# CPU.net
KiCad netlist of a schematic drawn in Altium Designer
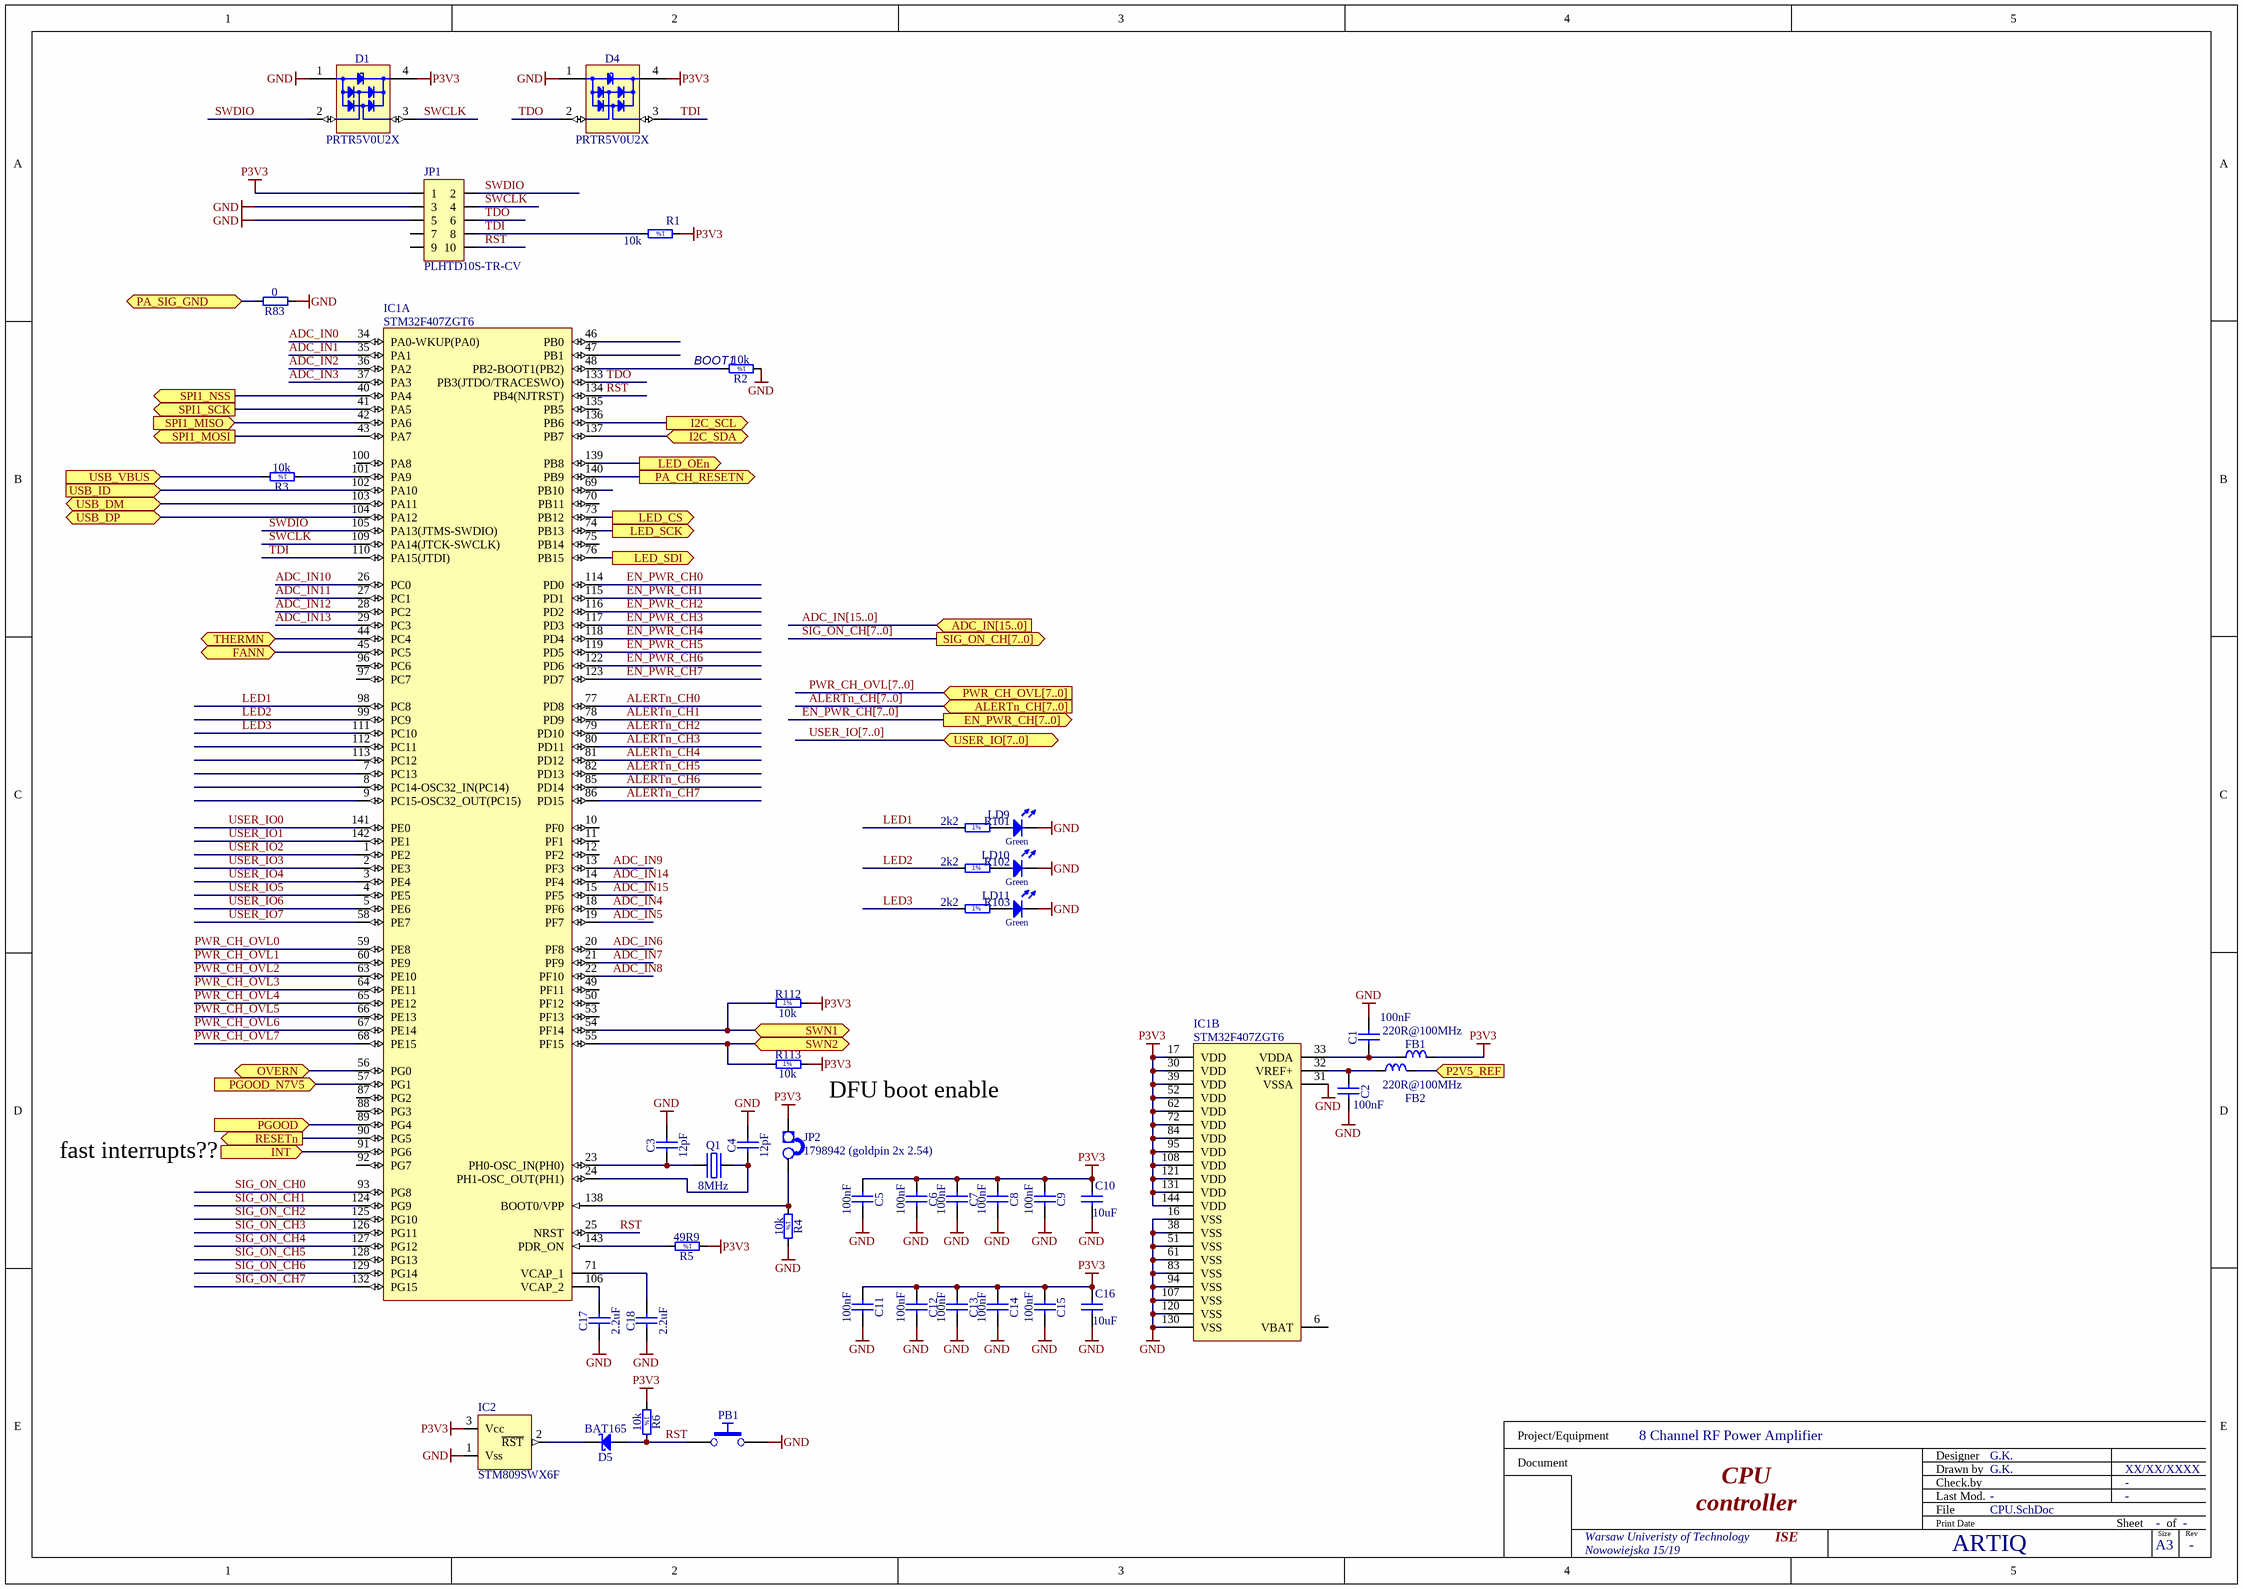
[diagram p0: CPU.SchDoc]

(export (version "E")
  (design (tool "Eeschema 10.0.6"))
  (components
    (comp (ref "C1")
      (value "100nF")
      (footprint "CAPC1005X55N")
      (description "Non-polarised capacitor")
      (fields
        (field (name "PART NUMBER") "CC0402_100NF_16V_10%_X7R")
        (field (name "VOLTAGE") "16V")
        (field (name "AUTHOR") "CERN DEM JLC")
      )
      (libsource (lib "Capacitors") (part "Capacitor - non polarized"))
    )
    (comp (ref "C2")
      (value "100nF")
      (footprint "CAPC1005X55N")
      (description "Non-polarised capacitor")
      (fields
        (field (name "PART NUMBER") "CC0402_100NF_16V_10%_X7R")
        (field (name "VOLTAGE") "16V")
        (field (name "AUTHOR") "CERN DEM JLC")
      )
      (libsource (lib "Capacitors") (part "Capacitor - non polarized"))
    )
    (comp (ref "C3")
      (value "12pF")
      (footprint "CAPC1005X55N")
      (description "Non-polarised capacitor")
      (fields
        (field (name "PART NUMBER") "CC0402_12PF_50V_5%_C0G")
        (field (name "VOLTAGE") "50V")
        (field (name "AUTHOR") "CERN DEM JLC")
      )
      (libsource (lib "Capacitors") (part "Capacitor - non polarized"))
    )
    (comp (ref "C4")
      (value "12pF")
      (footprint "CAPC1005X55N")
      (description "Non-polarised capacitor")
      (fields
        (field (name "PART NUMBER") "CC0402_12PF_50V_5%_C0G")
        (field (name "VOLTAGE") "50V")
        (field (name "AUTHOR") "CERN DEM JLC")
      )
      (libsource (lib "Capacitors") (part "Capacitor - non polarized"))
    )
    (comp (ref "C5")
      (value "100nF")
      (footprint "CAPC1005X55N")
      (description "Non-polarised capacitor")
      (fields
        (field (name "PART NUMBER") "CC0402_100NF_16V_10%_X7R")
        (field (name "VOLTAGE") "16V")
        (field (name "AUTHOR") "CERN DEM JLC")
      )
      (libsource (lib "Capacitors") (part "Capacitor - non polarized"))
    )
    (comp (ref "C6")
      (value "100nF")
      (footprint "CAPC1005X55N")
      (description "Non-polarised capacitor")
      (fields
        (field (name "PART NUMBER") "CC0402_100NF_16V_10%_X7R")
        (field (name "VOLTAGE") "16V")
        (field (name "AUTHOR") "CERN DEM JLC")
      )
      (libsource (lib "Capacitors") (part "Capacitor - non polarized"))
    )
    (comp (ref "C7")
      (value "100nF")
      (footprint "CAPC1005X55N")
      (description "Non-polarised capacitor")
      (fields
        (field (name "PART NUMBER") "CC0402_100NF_16V_10%_X7R")
        (field (name "VOLTAGE") "16V")
        (field (name "AUTHOR") "CERN DEM JLC")
      )
      (libsource (lib "Capacitors") (part "Capacitor - non polarized"))
    )
    (comp (ref "C8")
      (value "100nF")
      (footprint "CAPC1005X55N")
      (description "Non-polarised capacitor")
      (fields
        (field (name "PART NUMBER") "CC0402_100NF_16V_10%_X7R")
        (field (name "VOLTAGE") "16V")
        (field (name "AUTHOR") "CERN DEM JLC")
      )
      (libsource (lib "Capacitors") (part "Capacitor - non polarized"))
    )
    (comp (ref "C9")
      (value "100nF")
      (footprint "CAPC1005X55N")
      (description "Non-polarised capacitor")
      (fields
        (field (name "PART NUMBER") "CC0402_100NF_16V_10%_X7R")
        (field (name "VOLTAGE") "16V")
        (field (name "AUTHOR") "CERN DEM JLC")
      )
      (libsource (lib "Capacitors") (part "Capacitor - non polarized"))
    )
    (comp (ref "C10")
      (value "10uF")
      (footprint "CAPC2012X135N")
      (description "Non-polarised capacitor")
      (fields
        (field (name "PART NUMBER") "CC0805_10UF_10V_10%_X7R")
        (field (name "VOLTAGE") "10V")
        (field (name "AUTHOR") "CERN DEM JLC")
      )
      (libsource (lib "Capacitors") (part "Capacitor - non polarized"))
    )
    (comp (ref "C11")
      (value "100nF")
      (footprint "CAPC1005X55N")
      (description "Non-polarised capacitor")
      (fields
        (field (name "PART NUMBER") "CC0402_100NF_16V_10%_X7R")
        (field (name "VOLTAGE") "16V")
        (field (name "AUTHOR") "CERN DEM JLC")
      )
      (libsource (lib "Capacitors") (part "Capacitor - non polarized"))
    )
    (comp (ref "C12")
      (value "100nF")
      (footprint "CAPC1005X55N")
      (description "Non-polarised capacitor")
      (fields
        (field (name "PART NUMBER") "CC0402_100NF_16V_10%_X7R")
        (field (name "VOLTAGE") "16V")
        (field (name "AUTHOR") "CERN DEM JLC")
      )
      (libsource (lib "Capacitors") (part "Capacitor - non polarized"))
    )
    (comp (ref "C13")
      (value "100nF")
      (footprint "CAPC1005X55N")
      (description "Non-polarised capacitor")
      (fields
        (field (name "PART NUMBER") "CC0402_100NF_16V_10%_X7R")
        (field (name "VOLTAGE") "16V")
        (field (name "AUTHOR") "CERN DEM JLC")
      )
      (libsource (lib "Capacitors") (part "Capacitor - non polarized"))
    )
    (comp (ref "C14")
      (value "100nF")
      (footprint "CAPC1005X55N")
      (description "Non-polarised capacitor")
      (fields
        (field (name "PART NUMBER") "CC0402_100NF_16V_10%_X7R")
        (field (name "VOLTAGE") "16V")
        (field (name "AUTHOR") "CERN DEM JLC")
      )
      (libsource (lib "Capacitors") (part "Capacitor - non polarized"))
    )
    (comp (ref "C15")
      (value "100nF")
      (footprint "CAPC1005X55N")
      (description "Non-polarised capacitor")
      (fields
        (field (name "PART NUMBER") "CC0402_100NF_16V_10%_X7R")
        (field (name "VOLTAGE") "16V")
        (field (name "AUTHOR") "CERN DEM JLC")
      )
      (libsource (lib "Capacitors") (part "Capacitor - non polarized"))
    )
    (comp (ref "C16")
      (value "10uF")
      (footprint "CAPC2012X135N")
      (description "Non-polarised capacitor")
      (fields
        (field (name "PART NUMBER") "CC0805_10UF_10V_10%_X7R")
        (field (name "VOLTAGE") "10V")
        (field (name "AUTHOR") "CERN DEM JLC")
      )
      (libsource (lib "Capacitors") (part "Capacitor - non polarized"))
    )
    (comp (ref "C17")
      (value "2.2uF")
      (footprint "CAPC1608X90N")
      (description "Non-polarised capacitor")
      (fields
        (field (name "PART NUMBER") "CC0603_2.2UF_10V_20%_X7R")
        (field (name "VOLTAGE") "10V")
        (field (name "AUTHOR") "CERN DEM JLC")
      )
      (libsource (lib "Capacitors") (part "Capacitor - non polarized"))
    )
    (comp (ref "C18")
      (value "2.2uF")
      (footprint "CAPC1608X90N")
      (description "Non-polarised capacitor")
      (fields
        (field (name "PART NUMBER") "CC0603_2.2UF_10V_20%_X7R")
        (field (name "VOLTAGE") "10V")
        (field (name "AUTHOR") "CERN DEM JLC")
      )
      (libsource (lib "Capacitors") (part "Capacitor - non polarized"))
    )
    (comp (ref "D1")
      (value "PRTR5V0U2X")
      (footprint "SOT190P230X110-4N")
      (description "Ultra Low Capacitance Double Rail-to-Rail ESD Protection Diode")
      (fields
        (field (name "VOLTAGE") "5.5V")
        (field (name "MANUFACTURER") "NXP SEMICONDUCTORS")
        (field (name "AUTHOR") "CERN DEM JLC")
      )
      (libsource (lib "ICs And Semiconductors") (part "PRTR5V0U2X"))
    )
    (comp (ref "D4")
      (value "PRTR5V0U2X")
      (footprint "SOT190P230X110-4N")
      (description "Ultra Low Capacitance Double Rail-to-Rail ESD Protection Diode")
      (fields
        (field (name "VOLTAGE") "5.5V")
        (field (name "MANUFACTURER") "NXP SEMICONDUCTORS")
        (field (name "AUTHOR") "CERN DEM JLC")
      )
      (libsource (lib "ICs And Semiconductors") (part "PRTR5V0U2X"))
    )
    (comp (ref "D5")
      (value "BAT165")
      (footprint "SOD2512X110N")
      (description "Schottky Diode")
      (fields
        (field (name "VOLTAGE") "40V")
        (field (name "POWER") "750mA")
        (field (name "AUTHOR") "CERN DEM JLC")
      )
      (libsource (lib "ICs And Semiconductors") (part "Diode Schottky"))
    )
    (comp (ref "FB1")
      (value "220R@100MHz")
      (footprint "INDC2012X105N")
      (description "Inductor")
      (fields
        (field (name "PART NUMBER") "IND0805_MURATA_BLM21PG221SN1D")
        (field (name "POWER") "2A")
        (field (name "AUTHOR") "CERN DEM JLC")
      )
      (libsource (lib "Inductors & Transformers") (part "Inductor"))
    )
    (comp (ref "FB2")
      (value "220R@100MHz")
      (footprint "INDC2012X105N")
      (description "Inductor")
      (fields
        (field (name "PART NUMBER") "IND0805_MURATA_BLM21PG221SN1D")
        (field (name "POWER") "2A")
        (field (name "AUTHOR") "CERN DEM JLC")
      )
      (libsource (lib "Inductors & Transformers") (part "Inductor"))
    )
    (comp (ref "IC1")
      (value "STM32F407ZGT6")
      (footprint "QFP50P2200X2200X160-144N")
      (fields (field (name "MANUFACTURER") "ST MICROELECTRONICS") (field (name "AUTHOR") "CERN DEM MR"))
      (libsource (lib "ICs And Semiconductors") (part "STM32F407ZGT6"))
    )
    (comp (ref "IC2")
      (value "STM809SWX6F")
      (footprint "SOT-23")
      (description "2.93V  Reset circuit")
      (libsource (lib "LIBRARY_SCH") (part "VMON_STM809"))
    )
    (comp (ref "JP1")
      (value "PLHTD10S-TR-CV")
      (footprint "PLHTD10S-TR-CV")
      (description "1.27 mm dual row goldpin (Maritex)")
      (libsource (lib "LIBRARY_SCH") (part "CON_2x5 1.27 SMT Male"))
    )
    (comp (ref "JP2")
      (value "1798942 (goldpin 2x 2.54)")
      (footprint "jump")
      (description "Jumper")
      (libsource (lib "LIBRARY_SCH") (part "JUMPER"))
    )
    (comp (ref "LD9")
      (value "Green")
      (footprint "LED_OSRAM_LGL29K")
      (description "LED Green 1C 2A")
      (fields
        (field (name "PART NUMBER") "LED_OSRAM_LG L29K-G2J1-24-Z")
        (field (name "MANUFACTURER") "OSRAM")
        (field (name "AUTHOR") "CERN DEM JLC")
      )
      (libsource (lib "ICs And Semiconductors") (part "LED Green 1C 2A"))
    )
    (comp (ref "LD10")
      (value "Green")
      (footprint "LED_OSRAM_LGL29K")
      (description "LED Green 1C 2A")
      (fields
        (field (name "PART NUMBER") "LED_OSRAM_LG L29K-G2J1-24-Z")
        (field (name "MANUFACTURER") "OSRAM")
        (field (name "AUTHOR") "CERN DEM JLC")
      )
      (libsource (lib "ICs And Semiconductors") (part "LED Green 1C 2A"))
    )
    (comp (ref "LD11")
      (value "Green")
      (footprint "LED_OSRAM_LGL29K")
      (description "LED Green 1C 2A")
      (fields
        (field (name "PART NUMBER") "LED_OSRAM_LG L29K-G2J1-24-Z")
        (field (name "MANUFACTURER") "OSRAM")
        (field (name "AUTHOR") "CERN DEM JLC")
      )
      (libsource (lib "ICs And Semiconductors") (part "LED Green 1C 2A"))
    )
    (comp (ref "PB1")
      (value "Push Button")
      (footprint "PB_TYCO_FSMSM")
      (description "Push-Button Switch SPDT")
      (fields
        (field (name "PART NUMBER") "PB_TYCO_FSMSM")
        (field (name "MANUFACTURER") "TYCO ELECTRONICS")
        (field (name "AUTHOR") "CERN DEM JLC")
      )
      (libsource (lib "Eletro-mechanical") (part "PB SPST 1NO-2NO"))
    )
    (comp (ref "Q1")
      (value "8MHz")
      (footprint "XTAL_TXC_7A")
      (description "Quartz Crystal")
      (fields
        (field (name "PART NUMBER") "XTAL_8MHZ_TXC_7A-8.000MAAE-T")
        (field (name "MANUFACTURER") "TXC CORPORATION")
        (field (name "AUTHOR") "CERN DEM JLC")
      )
      (libsource (lib "ICs And Semiconductors") (part "Quartz Crystal"))
    )
    (comp (ref "R1")
      (value "10k")
      (footprint "RESC1005X40N")
      (description "Resistor - 1%")
      (fields
        (field (name "PART NUMBER") "R0402_10K_1%_0.0625W_100PPM")
        (field (name "POWER") "0.0625W")
        (field (name "AUTHOR") "CERN DEM JLC")
      )
      (libsource (lib "Resistors") (part "Resistor - 1%"))
    )
    (comp (ref "R2")
      (value "10k")
      (footprint "RESC1005X40N")
      (description "Resistor - 1%")
      (fields
        (field (name "PART NUMBER") "R0402_10K_1%_0.0625W_100PPM")
        (field (name "POWER") "0.0625W")
        (field (name "AUTHOR") "CERN DEM JLC")
      )
      (libsource (lib "Resistors") (part "Resistor - 1%"))
    )
    (comp (ref "R3")
      (value "10k")
      (footprint "RESC1005X40N")
      (description "Resistor - 1%")
      (fields
        (field (name "PART NUMBER") "R0402_10K_1%_0.0625W_100PPM")
        (field (name "POWER") "0.0625W")
        (field (name "AUTHOR") "CERN DEM JLC")
      )
      (libsource (lib "Resistors") (part "Resistor - 1%"))
    )
    (comp (ref "R4")
      (value "10k")
      (footprint "RESC1005X40N")
      (description "Resistor - 1%")
      (fields
        (field (name "PART NUMBER") "R0402_10K_1%_0.0625W_100PPM")
        (field (name "POWER") "0.0625W")
        (field (name "AUTHOR") "CERN DEM JLC")
      )
      (libsource (lib "Resistors") (part "Resistor - 1%"))
    )
    (comp (ref "R5")
      (value "49R9")
      (footprint "RESC1005X40N")
      (description "Resistor - 1%")
      (fields
        (field (name "PART NUMBER") "R0402_49R9_1%_0.0625W_100PPM")
        (field (name "POWER") "0.0625W")
        (field (name "AUTHOR") "CERN DEM JLC")
      )
      (libsource (lib "Resistors") (part "Resistor - 1%"))
    )
    (comp (ref "R6")
      (value "10k")
      (footprint "RESC1005X40N")
      (description "Resistor - 1%")
      (fields
        (field (name "PART NUMBER") "R0402_10K_1%_0.0625W_100PPM")
        (field (name "POWER") "0.0625W")
        (field (name "AUTHOR") "CERN DEM JLC")
      )
      (libsource (lib "Resistors") (part "Resistor - 1%"))
    )
    (comp (ref "R83")
      (value "0")
      (footprint "RESC1005X40N")
      (description "Resistor")
      (fields
        (field (name "PART NUMBER") "R0402_0R_JUMPER")
        (field (name "MANUFACTURER") "GENERIC")
        (field (name "AUTHOR") "CERN DEM JLC")
      )
      (libsource (lib "Resistors") (part "Resistor"))
    )
    (comp (ref "R101")
      (value "2k2")
      (footprint "RESC1005X40N")
      (description "Resistor - 1%")
      (fields
        (field (name "PART NUMBER") "R0402_2K2_1%_0.0625W_100PPM")
        (field (name "POWER") "0.0625W")
        (field (name "AUTHOR") "CERN DEM JLC")
      )
      (libsource (lib "Resistors") (part "Resistor - 1%"))
    )
    (comp (ref "R102")
      (value "2k2")
      (footprint "RESC1005X40N")
      (description "Resistor - 1%")
      (fields
        (field (name "PART NUMBER") "R0402_2K2_1%_0.0625W_100PPM")
        (field (name "POWER") "0.0625W")
        (field (name "AUTHOR") "CERN DEM JLC")
      )
      (libsource (lib "Resistors") (part "Resistor - 1%"))
    )
    (comp (ref "R103")
      (value "2k2")
      (footprint "RESC1005X40N")
      (description "Resistor - 1%")
      (fields
        (field (name "PART NUMBER") "R0402_2K2_1%_0.0625W_100PPM")
        (field (name "POWER") "0.0625W")
        (field (name "AUTHOR") "CERN DEM JLC")
      )
      (libsource (lib "Resistors") (part "Resistor - 1%"))
    )
    (comp (ref "R112")
      (value "10k")
      (footprint "RESC1005X40N")
      (description "Resistor - 1%")
      (fields
        (field (name "PART NUMBER") "R0402_10K_1%_0.0625W_100PPM")
        (field (name "POWER") "0.0625W")
        (field (name "AUTHOR") "CERN DEM JLC")
      )
      (libsource (lib "Resistors") (part "Resistor - 1%"))
    )
    (comp (ref "R113")
      (value "10k")
      (footprint "RESC1005X40N")
      (description "Resistor - 1%")
      (fields
        (field (name "PART NUMBER") "R0402_10K_1%_0.0625W_100PPM")
        (field (name "POWER") "0.0625W")
        (field (name "AUTHOR") "CERN DEM JLC")
      )
      (libsource (lib "Resistors") (part "Resistor - 1%"))
    )
  )
  (nets
    (net (code "1") (name "/ADC_IN0") (class "Default")
      (node (ref "IC1") (pin "34") (pinfunction "PA0-WKUP(PA0)_34") (pintype "bidirectional"))
    )
    (net (code "2") (name "/ADC_IN1") (class "Default")
      (node (ref "IC1") (pin "35") (pinfunction "PA1_35") (pintype "bidirectional"))
    )
    (net (code "3") (name "/ADC_IN2") (class "Default")
      (node (ref "IC1") (pin "36") (pinfunction "PA2_36") (pintype "bidirectional"))
    )
    (net (code "4") (name "/ADC_IN3") (class "Default")
      (node (ref "IC1") (pin "37") (pinfunction "PA3_37") (pintype "bidirectional"))
    )
    (net (code "5") (name "/ADC_IN4") (class "Default")
      (node (ref "IC1") (pin "18") (pinfunction "PF6_18") (pintype "bidirectional"))
    )
    (net (code "6") (name "/ADC_IN5") (class "Default")
      (node (ref "IC1") (pin "19") (pinfunction "PF7_19") (pintype "bidirectional"))
    )
    (net (code "7") (name "/ADC_IN6") (class "Default")
      (node (ref "IC1") (pin "20") (pinfunction "PF8_20") (pintype "bidirectional"))
    )
    (net (code "8") (name "/ADC_IN7") (class "Default")
      (node (ref "IC1") (pin "21") (pinfunction "PF9_21") (pintype "bidirectional"))
    )
    (net (code "9") (name "/ADC_IN8") (class "Default")
      (node (ref "IC1") (pin "22") (pinfunction "PF10_22") (pintype "bidirectional"))
    )
    (net (code "10") (name "/ADC_IN9") (class "Default")
      (node (ref "IC1") (pin "13") (pinfunction "PF3_13") (pintype "bidirectional"))
    )
    (net (code "11") (name "/ADC_IN10") (class "Default")
      (node (ref "IC1") (pin "26") (pinfunction "PC0_26") (pintype "bidirectional"))
    )
    (net (code "12") (name "/ADC_IN11") (class "Default")
      (node (ref "IC1") (pin "27") (pinfunction "PC1_27") (pintype "bidirectional"))
    )
    (net (code "13") (name "/ADC_IN12") (class "Default")
      (node (ref "IC1") (pin "28") (pinfunction "PC2_28") (pintype "bidirectional"))
    )
    (net (code "14") (name "/ADC_IN13") (class "Default")
      (node (ref "IC1") (pin "29") (pinfunction "PC3_29") (pintype "bidirectional"))
    )
    (net (code "15") (name "/ADC_IN14") (class "Default")
      (node (ref "IC1") (pin "14") (pinfunction "PF4_14") (pintype "bidirectional"))
    )
    (net (code "16") (name "/ADC_IN15") (class "Default")
      (node (ref "IC1") (pin "15") (pinfunction "PF5_15") (pintype "bidirectional"))
    )
    (net (code "18") (name "/ALERTn_CH0") (class "Default")
      (node (ref "IC1") (pin "77") (pinfunction "PD8_77") (pintype "bidirectional"))
    )
    (net (code "19") (name "/ALERTn_CH1") (class "Default")
      (node (ref "IC1") (pin "78") (pinfunction "PD9_78") (pintype "bidirectional"))
    )
    (net (code "20") (name "/ALERTn_CH2") (class "Default")
      (node (ref "IC1") (pin "79") (pinfunction "PD10_79") (pintype "bidirectional"))
    )
    (net (code "21") (name "/ALERTn_CH3") (class "Default")
      (node (ref "IC1") (pin "80") (pinfunction "PD11_80") (pintype "bidirectional"))
    )
    (net (code "22") (name "/ALERTn_CH4") (class "Default")
      (node (ref "IC1") (pin "81") (pinfunction "PD12_81") (pintype "bidirectional"))
    )
    (net (code "23") (name "/ALERTn_CH5") (class "Default")
      (node (ref "IC1") (pin "82") (pinfunction "PD13_82") (pintype "bidirectional"))
    )
    (net (code "24") (name "/ALERTn_CH6") (class "Default")
      (node (ref "IC1") (pin "85") (pinfunction "PD14_85") (pintype "bidirectional"))
    )
    (net (code "25") (name "/ALERTn_CH7") (class "Default")
      (node (ref "IC1") (pin "86") (pinfunction "PD15_86") (pintype "bidirectional"))
    )
    (net (code "27") (name "/EN_PWR_CH0") (class "Default")
      (node (ref "IC1") (pin "114") (pinfunction "PD0_114") (pintype "bidirectional"))
    )
    (net (code "28") (name "/EN_PWR_CH1") (class "Default")
      (node (ref "IC1") (pin "115") (pinfunction "PD1_115") (pintype "bidirectional"))
    )
    (net (code "29") (name "/EN_PWR_CH2") (class "Default")
      (node (ref "IC1") (pin "116") (pinfunction "PD2_116") (pintype "bidirectional"))
    )
    (net (code "30") (name "/EN_PWR_CH3") (class "Default")
      (node (ref "IC1") (pin "117") (pinfunction "PD3_117") (pintype "bidirectional"))
    )
    (net (code "31") (name "/EN_PWR_CH4") (class "Default")
      (node (ref "IC1") (pin "118") (pinfunction "PD4_118") (pintype "bidirectional"))
    )
    (net (code "32") (name "/EN_PWR_CH5") (class "Default")
      (node (ref "IC1") (pin "119") (pinfunction "PD5_119") (pintype "bidirectional"))
    )
    (net (code "33") (name "/EN_PWR_CH6") (class "Default")
      (node (ref "IC1") (pin "122") (pinfunction "PD6_122") (pintype "bidirectional"))
    )
    (net (code "34") (name "/EN_PWR_CH7") (class "Default")
      (node (ref "IC1") (pin "123") (pinfunction "PD7_123") (pintype "bidirectional"))
    )
    (net (code "36") (name "/FANN") (class "Default")
      (node (ref "IC1") (pin "45") (pinfunction "PC5_45") (pintype "bidirectional"))
    )
    (net (code "37") (name "/I2C_SCL") (class "Default")
      (node (ref "IC1") (pin "136") (pinfunction "PB6_136") (pintype "bidirectional"))
    )
    (net (code "38") (name "/I2C_SDA") (class "Default")
      (node (ref "IC1") (pin "137") (pinfunction "PB7_137") (pintype "bidirectional"))
    )
    (net (code "39") (name "/INT") (class "Default")
      (node (ref "IC1") (pin "91") (pinfunction "PG6_91") (pintype "bidirectional"))
    )
    (net (code "40") (name "/LED1") (class "Default")
      (node (ref "IC1") (pin "98") (pinfunction "PC8_98") (pintype "bidirectional"))
      (node (ref "R101") (pin "1") (pinfunction "1_1") (pintype "passive"))
    )
    (net (code "41") (name "/LED2") (class "Default")
      (node (ref "IC1") (pin "99") (pinfunction "PC9_99") (pintype "bidirectional"))
      (node (ref "R102") (pin "1") (pinfunction "1_1") (pintype "passive"))
    )
    (net (code "42") (name "/LED3") (class "Default")
      (node (ref "IC1") (pin "111") (pinfunction "PC10_111") (pintype "bidirectional"))
      (node (ref "R103") (pin "1") (pinfunction "1_1") (pintype "passive"))
    )
    (net (code "43") (name "/LED_CS") (class "Default")
      (node (ref "IC1") (pin "73") (pinfunction "PB12_73") (pintype "bidirectional"))
    )
    (net (code "44") (name "/LED_OEn") (class "Default")
      (node (ref "IC1") (pin "139") (pinfunction "PB8_139") (pintype "bidirectional"))
    )
    (net (code "45") (name "/LED_SCK") (class "Default")
      (node (ref "IC1") (pin "74") (pinfunction "PB13_74") (pintype "bidirectional"))
    )
    (net (code "46") (name "/LED_SDI") (class "Default")
      (node (ref "IC1") (pin "76") (pinfunction "PB15_76") (pintype "bidirectional"))
    )
    (net (code "47") (name "/OVERN") (class "Default")
      (node (ref "IC1") (pin "56") (pinfunction "PG0_56") (pintype "bidirectional"))
    )
    (net (code "48") (name "/P2V5_REF") (class "Default")
      (node (ref "FB2") (pin "2") (pinfunction "2_2") (pintype "passive"))
    )
    (net (code "49") (name "/PA_CH_RESETN") (class "Default")
      (node (ref "IC1") (pin "140") (pinfunction "PB9_140") (pintype "bidirectional"))
    )
    (net (code "50") (name "/PA_SIG_GND") (class "Default")
      (node (ref "R83") (pin "2") (pinfunction "2_2") (pintype "passive"))
    )
    (net (code "51") (name "/PGOOD") (class "Default")
      (node (ref "IC1") (pin "89") (pinfunction "PG4_89") (pintype "bidirectional"))
    )
    (net (code "52") (name "/PGOOD_N7V5") (class "Default")
      (node (ref "IC1") (pin "57") (pinfunction "PG1_57") (pintype "bidirectional"))
    )
    (net (code "53") (name "/PWR_CH_OVL0") (class "Default")
      (node (ref "IC1") (pin "59") (pinfunction "PE8_59") (pintype "bidirectional"))
    )
    (net (code "54") (name "/PWR_CH_OVL1") (class "Default")
      (node (ref "IC1") (pin "60") (pinfunction "PE9_60") (pintype "bidirectional"))
    )
    (net (code "55") (name "/PWR_CH_OVL2") (class "Default")
      (node (ref "IC1") (pin "63") (pinfunction "PE10_63") (pintype "bidirectional"))
    )
    (net (code "56") (name "/PWR_CH_OVL3") (class "Default")
      (node (ref "IC1") (pin "64") (pinfunction "PE11_64") (pintype "bidirectional"))
    )
    (net (code "57") (name "/PWR_CH_OVL4") (class "Default")
      (node (ref "IC1") (pin "65") (pinfunction "PE12_65") (pintype "bidirectional"))
    )
    (net (code "58") (name "/PWR_CH_OVL5") (class "Default")
      (node (ref "IC1") (pin "66") (pinfunction "PE13_66") (pintype "bidirectional"))
    )
    (net (code "59") (name "/PWR_CH_OVL6") (class "Default")
      (node (ref "IC1") (pin "67") (pinfunction "PE14_67") (pintype "bidirectional"))
    )
    (net (code "60") (name "/PWR_CH_OVL7") (class "Default")
      (node (ref "IC1") (pin "68") (pinfunction "PE15_68") (pintype "bidirectional"))
    )
    (net (code "62") (name "/RESETn") (class "Default")
      (node (ref "IC1") (pin "90") (pinfunction "PG5_90") (pintype "bidirectional"))
    )
    (net (code "63") (name "/RST") (class "Default")
      (node (ref "D5") (pin "2") (pinfunction "A_2") (pintype "passive"))
      (node (ref "IC1") (pin "134") (pinfunction "PB4(NJTRST)_134") (pintype "bidirectional"))
      (node (ref "IC1") (pin "25") (pinfunction "NRST_25") (pintype "bidirectional"))
      (node (ref "JP1") (pin "10") (pinfunction "10_10") (pintype "passive"))
      (node (ref "PB1") (pin "1") (pinfunction "1_1") (pintype "passive"))
      (node (ref "R6") (pin "2") (pinfunction "2_2") (pintype "passive"))
    )
    (net (code "64") (name "/SIG_ON_CH0") (class "Default")
      (node (ref "IC1") (pin "93") (pinfunction "PG8_93") (pintype "bidirectional"))
    )
    (net (code "65") (name "/SIG_ON_CH1") (class "Default")
      (node (ref "IC1") (pin "124") (pinfunction "PG9_124") (pintype "bidirectional"))
    )
    (net (code "66") (name "/SIG_ON_CH2") (class "Default")
      (node (ref "IC1") (pin "125") (pinfunction "PG10_125") (pintype "bidirectional"))
    )
    (net (code "67") (name "/SIG_ON_CH3") (class "Default")
      (node (ref "IC1") (pin "126") (pinfunction "PG11_126") (pintype "bidirectional"))
    )
    (net (code "68") (name "/SIG_ON_CH4") (class "Default")
      (node (ref "IC1") (pin "127") (pinfunction "PG12_127") (pintype "bidirectional"))
    )
    (net (code "69") (name "/SIG_ON_CH5") (class "Default")
      (node (ref "IC1") (pin "128") (pinfunction "PG13_128") (pintype "bidirectional"))
    )
    (net (code "70") (name "/SIG_ON_CH6") (class "Default")
      (node (ref "IC1") (pin "129") (pinfunction "PG14_129") (pintype "bidirectional"))
    )
    (net (code "71") (name "/SIG_ON_CH7") (class "Default")
      (node (ref "IC1") (pin "132") (pinfunction "PG15_132") (pintype "bidirectional"))
    )
    (net (code "73") (name "/SPI1_MISO") (class "Default")
      (node (ref "IC1") (pin "42") (pinfunction "PA6_42") (pintype "bidirectional"))
    )
    (net (code "74") (name "/SPI1_MOSI") (class "Default")
      (node (ref "IC1") (pin "43") (pinfunction "PA7_43") (pintype "bidirectional"))
    )
    (net (code "75") (name "/SPI1_NSS") (class "Default")
      (node (ref "IC1") (pin "40") (pinfunction "PA4_40") (pintype "bidirectional"))
    )
    (net (code "76") (name "/SPI1_SCK") (class "Default")
      (node (ref "IC1") (pin "41") (pinfunction "PA5_41") (pintype "bidirectional"))
    )
    (net (code "77") (name "/SWCLK") (class "Default")
      (node (ref "D1") (pin "3") (pinfunction "I/O2_3") (pintype "bidirectional"))
      (node (ref "IC1") (pin "109") (pinfunction "PA14(JTCK-SWCLK)_109") (pintype "bidirectional"))
      (node (ref "JP1") (pin "4") (pinfunction "4_4") (pintype "passive"))
    )
    (net (code "78") (name "/SWDIO") (class "Default")
      (node (ref "D1") (pin "2") (pinfunction "I/O1_2") (pintype "bidirectional"))
      (node (ref "IC1") (pin "105") (pinfunction "PA13(JTMS-SWDIO)_105") (pintype "bidirectional"))
      (node (ref "JP1") (pin "2") (pinfunction "2_2") (pintype "passive"))
    )
    (net (code "79") (name "/SWN1") (class "Default")
      (node (ref "IC1") (pin "54") (pinfunction "PF14_54") (pintype "bidirectional"))
      (node (ref "R112") (pin "1") (pinfunction "1_1") (pintype "passive"))
    )
    (net (code "80") (name "/SWN2") (class "Default")
      (node (ref "IC1") (pin "55") (pinfunction "PF15_55") (pintype "bidirectional"))
      (node (ref "R113") (pin "1") (pinfunction "1_1") (pintype "passive"))
    )
    (net (code "81") (name "/TDI") (class "Default")
      (node (ref "D4") (pin "3") (pinfunction "I/O2_3") (pintype "bidirectional"))
      (node (ref "IC1") (pin "110") (pinfunction "PA15(JTDI)_110") (pintype "bidirectional"))
      (node (ref "JP1") (pin "8") (pinfunction "8_8") (pintype "passive"))
      (node (ref "R1") (pin "2") (pinfunction "2_2") (pintype "passive"))
    )
    (net (code "82") (name "/TDO") (class "Default")
      (node (ref "D4") (pin "2") (pinfunction "I/O1_2") (pintype "bidirectional"))
      (node (ref "IC1") (pin "133") (pinfunction "PB3(JTDO/TRACESWO)_133") (pintype "bidirectional"))
      (node (ref "JP1") (pin "6") (pinfunction "6_6") (pintype "passive"))
    )
    (net (code "83") (name "/THERMN") (class "Default")
      (node (ref "IC1") (pin "44") (pinfunction "PC4_44") (pintype "bidirectional"))
    )
    (net (code "84") (name "/USB_DM") (class "Default")
      (node (ref "IC1") (pin "103") (pinfunction "PA11_103") (pintype "bidirectional"))
    )
    (net (code "85") (name "/USB_DP") (class "Default")
      (node (ref "IC1") (pin "104") (pinfunction "PA12_104") (pintype "bidirectional"))
    )
    (net (code "86") (name "/USB_ID") (class "Default")
      (node (ref "IC1") (pin "102") (pinfunction "PA10_102") (pintype "bidirectional"))
    )
    (net (code "87") (name "/USB_VBUS") (class "Default")
      (node (ref "R3") (pin "2") (pinfunction "2_2") (pintype "passive"))
    )
    (net (code "88") (name "/USER_IO0") (class "Default")
      (node (ref "IC1") (pin "141") (pinfunction "PE0_141") (pintype "bidirectional"))
    )
    (net (code "89") (name "/USER_IO1") (class "Default")
      (node (ref "IC1") (pin "142") (pinfunction "PE1_142") (pintype "bidirectional"))
    )
    (net (code "90") (name "/USER_IO2") (class "Default")
      (node (ref "IC1") (pin "1") (pinfunction "PE2_1") (pintype "bidirectional"))
    )
    (net (code "91") (name "/USER_IO3") (class "Default")
      (node (ref "IC1") (pin "2") (pinfunction "PE3_2") (pintype "bidirectional"))
    )
    (net (code "92") (name "/USER_IO4") (class "Default")
      (node (ref "IC1") (pin "3") (pinfunction "PE4_3") (pintype "bidirectional"))
    )
    (net (code "93") (name "/USER_IO5") (class "Default")
      (node (ref "IC1") (pin "4") (pinfunction "PE5_4") (pintype "bidirectional"))
    )
    (net (code "94") (name "/USER_IO6") (class "Default")
      (node (ref "IC1") (pin "5") (pinfunction "PE6_5") (pintype "bidirectional"))
    )
    (net (code "95") (name "/USER_IO7") (class "Default")
      (node (ref "IC1") (pin "58") (pinfunction "PE7_58") (pintype "bidirectional"))
    )
    (net (code "97") (name "GND") (class "Default")
      (node (ref "C1") (pin "2") (pinfunction "2_2") (pintype "passive"))
      (node (ref "C10") (pin "2") (pinfunction "2_2") (pintype "passive"))
      (node (ref "C11") (pin "2") (pinfunction "2_2") (pintype "passive"))
      (node (ref "C12") (pin "2") (pinfunction "2_2") (pintype "passive"))
      (node (ref "C13") (pin "2") (pinfunction "2_2") (pintype "passive"))
      (node (ref "C14") (pin "2") (pinfunction "2_2") (pintype "passive"))
      (node (ref "C15") (pin "2") (pinfunction "2_2") (pintype "passive"))
      (node (ref "C16") (pin "2") (pinfunction "2_2") (pintype "passive"))
      (node (ref "C17") (pin "1") (pinfunction "1_1") (pintype "passive"))
      (node (ref "C18") (pin "1") (pinfunction "1_1") (pintype "passive"))
      (node (ref "C2") (pin "2") (pinfunction "2_2") (pintype "passive"))
      (node (ref "C3") (pin "2") (pinfunction "2_2") (pintype "passive"))
      (node (ref "C4") (pin "2") (pinfunction "2_2") (pintype "passive"))
      (node (ref "C5") (pin "2") (pinfunction "2_2") (pintype "passive"))
      (node (ref "C6") (pin "2") (pinfunction "2_2") (pintype "passive"))
      (node (ref "C7") (pin "2") (pinfunction "2_2") (pintype "passive"))
      (node (ref "C8") (pin "2") (pinfunction "2_2") (pintype "passive"))
      (node (ref "C9") (pin "2") (pinfunction "2_2") (pintype "passive"))
      (node (ref "D1") (pin "1") (pinfunction "GND_1") (pintype "power_in"))
      (node (ref "D4") (pin "1") (pinfunction "GND_1") (pintype "power_in"))
      (node (ref "IC1") (pin "107") (pinfunction "VSS_107") (pintype "power_in"))
      (node (ref "IC1") (pin "120") (pinfunction "VSS_120") (pintype "power_in"))
      (node (ref "IC1") (pin "130") (pinfunction "VSS_130") (pintype "power_in"))
      (node (ref "IC1") (pin "16") (pinfunction "VSS_16") (pintype "power_in"))
      (node (ref "IC1") (pin "31") (pinfunction "VSSA_31") (pintype "power_in"))
      (node (ref "IC1") (pin "38") (pinfunction "VSS_38") (pintype "power_in"))
      (node (ref "IC1") (pin "51") (pinfunction "VSS_51") (pintype "power_in"))
      (node (ref "IC1") (pin "61") (pinfunction "VSS_61") (pintype "power_in"))
      (node (ref "IC1") (pin "83") (pinfunction "VSS_83") (pintype "power_in"))
      (node (ref "IC1") (pin "94") (pinfunction "VSS_94") (pintype "power_in"))
      (node (ref "IC2") (pin "1") (pinfunction "Vss_1") (pintype "power_in"))
      (node (ref "JP1") (pin "3") (pinfunction "3_3") (pintype "passive"))
      (node (ref "JP1") (pin "5") (pinfunction "5_5") (pintype "passive"))
      (node (ref "LD10") (pin "1") (pinfunction "C_1") (pintype "passive"))
      (node (ref "LD11") (pin "1") (pinfunction "C_1") (pintype "passive"))
      (node (ref "LD9") (pin "1") (pinfunction "C_1") (pintype "passive"))
      (node (ref "PB1") (pin "2") (pinfunction "2_2") (pintype "passive"))
      (node (ref "R2") (pin "1") (pinfunction "1_1") (pintype "passive"))
      (node (ref "R4") (pin "2") (pinfunction "2_2") (pintype "passive"))
      (node (ref "R83") (pin "1") (pinfunction "1_1") (pintype "passive"))
    )
    (net (code "98") (name "Net-(D5-C)") (class "Default")
      (node (ref "D5") (pin "1") (pinfunction "C_1") (pintype "passive"))
      (node (ref "IC2") (pin "2") (pinfunction "~{RST}_2") (pintype "output"))
    )
    (net (code "99") (name "Net-(IC1A-BOOT0{slash}VPP)") (class "Default")
      (node (ref "IC1") (pin "138") (pinfunction "BOOT0/VPP_138") (pintype "input"))
      (node (ref "JP2") (pin "2") (pinfunction "E2_2") (pintype "passive"))
      (node (ref "R4") (pin "1") (pinfunction "1_1") (pintype "passive"))
    )
    (net (code "100") (name "Net-(IC1A-PA9)") (class "Default")
      (node (ref "IC1") (pin "101") (pinfunction "PA9_101") (pintype "bidirectional"))
      (node (ref "R3") (pin "1") (pinfunction "1_1") (pintype "passive"))
    )
    (net (code "101") (name "Net-(IC1A-PB2-BOOT1(PB2))") (class "Default")
      (node (ref "IC1") (pin "48") (pinfunction "PB2-BOOT1(PB2)_48") (pintype "bidirectional"))
      (node (ref "R2") (pin "2") (pinfunction "2_2") (pintype "passive"))
    )
    (net (code "102") (name "Net-(IC1A-PDR_ON)") (class "Default")
      (node (ref "IC1") (pin "143") (pinfunction "PDR_ON_143") (pintype "input"))
      (node (ref "R5") (pin "2") (pinfunction "2_2") (pintype "passive"))
    )
    (net (code "103") (name "Net-(IC1A-PH0-OSC_IN(PH0))") (class "Default")
      (node (ref "C3") (pin "1") (pinfunction "1_1") (pintype "passive"))
      (node (ref "IC1") (pin "23") (pinfunction "PH0-OSC_IN(PH0)_23") (pintype "bidirectional"))
      (node (ref "Q1") (pin "1") (pinfunction "OSC1_1") (pintype "passive"))
    )
    (net (code "104") (name "Net-(IC1A-PH1-OSC_OUT(PH1))") (class "Default")
      (node (ref "C4") (pin "1") (pinfunction "1_1") (pintype "passive"))
      (node (ref "IC1") (pin "24") (pinfunction "PH1-OSC_OUT(PH1)_24") (pintype "bidirectional"))
      (node (ref "Q1") (pin "2") (pinfunction "OSC2_2") (pintype "passive"))
    )
    (net (code "105") (name "Net-(IC1A-VCAP_1)") (class "Default")
      (node (ref "C18") (pin "2") (pinfunction "2_2") (pintype "passive"))
      (node (ref "IC1") (pin "71") (pinfunction "VCAP_1_71") (pintype "power_in"))
    )
    (net (code "106") (name "Net-(IC1A-VCAP_2)") (class "Default")
      (node (ref "C17") (pin "2") (pinfunction "2_2") (pintype "passive"))
      (node (ref "IC1") (pin "106") (pinfunction "VCAP_2_106") (pintype "power_in"))
    )
    (net (code "107") (name "Net-(IC1B-VDDA)") (class "Default")
      (node (ref "C1") (pin "1") (pinfunction "1_1") (pintype "passive"))
      (node (ref "FB1") (pin "1") (pinfunction "1_1") (pintype "passive"))
      (node (ref "IC1") (pin "33") (pinfunction "VDDA_33") (pintype "power_in"))
    )
    (net (code "108") (name "Net-(IC1B-VREF+)") (class "Default")
      (node (ref "C2") (pin "1") (pinfunction "1_1") (pintype "passive"))
      (node (ref "FB2") (pin "1") (pinfunction "1_1") (pintype "passive"))
      (node (ref "IC1") (pin "32") (pinfunction "VREF+_32") (pintype "power_in"))
    )
    (net (code "109") (name "Net-(LD9-A)") (class "Default")
      (node (ref "LD9") (pin "2") (pinfunction "A_2") (pintype "passive"))
      (node (ref "R101") (pin "2") (pinfunction "2_2") (pintype "passive"))
    )
    (net (code "110") (name "Net-(LD10-A)") (class "Default")
      (node (ref "LD10") (pin "2") (pinfunction "A_2") (pintype "passive"))
      (node (ref "R102") (pin "2") (pinfunction "2_2") (pintype "passive"))
    )
    (net (code "111") (name "Net-(LD11-A)") (class "Default")
      (node (ref "LD11") (pin "2") (pinfunction "A_2") (pintype "passive"))
      (node (ref "R103") (pin "2") (pinfunction "2_2") (pintype "passive"))
    )
    (net (code "112") (name "P3V3") (class "Default")
      (node (ref "C10") (pin "1") (pinfunction "1_1") (pintype "passive"))
      (node (ref "C11") (pin "1") (pinfunction "1_1") (pintype "passive"))
      (node (ref "C12") (pin "1") (pinfunction "1_1") (pintype "passive"))
      (node (ref "C13") (pin "1") (pinfunction "1_1") (pintype "passive"))
      (node (ref "C14") (pin "1") (pinfunction "1_1") (pintype "passive"))
      (node (ref "C15") (pin "1") (pinfunction "1_1") (pintype "passive"))
      (node (ref "C16") (pin "1") (pinfunction "1_1") (pintype "passive"))
      (node (ref "C5") (pin "1") (pinfunction "1_1") (pintype "passive"))
      (node (ref "C6") (pin "1") (pinfunction "1_1") (pintype "passive"))
      (node (ref "C7") (pin "1") (pinfunction "1_1") (pintype "passive"))
      (node (ref "C8") (pin "1") (pinfunction "1_1") (pintype "passive"))
      (node (ref "C9") (pin "1") (pinfunction "1_1") (pintype "passive"))
      (node (ref "D1") (pin "4") (pinfunction "VCC_4") (pintype "power_in"))
      (node (ref "D4") (pin "4") (pinfunction "VCC_4") (pintype "power_in"))
      (node (ref "FB1") (pin "2") (pinfunction "2_2") (pintype "passive"))
      (node (ref "IC1") (pin "108") (pinfunction "VDD_108") (pintype "power_in"))
      (node (ref "IC1") (pin "121") (pinfunction "VDD_121") (pintype "power_in"))
      (node (ref "IC1") (pin "131") (pinfunction "VDD_131") (pintype "power_in"))
      (node (ref "IC1") (pin "144") (pinfunction "VDD_144") (pintype "power_in"))
      (node (ref "IC1") (pin "17") (pinfunction "VDD_17") (pintype "power_in"))
      (node (ref "IC1") (pin "30") (pinfunction "VDD_30") (pintype "power_in"))
      (node (ref "IC1") (pin "39") (pinfunction "VDD_39") (pintype "power_in"))
      (node (ref "IC1") (pin "52") (pinfunction "VDD_52") (pintype "power_in"))
      (node (ref "IC1") (pin "62") (pinfunction "VDD_62") (pintype "power_in"))
      (node (ref "IC1") (pin "72") (pinfunction "VDD_72") (pintype "power_in"))
      (node (ref "IC1") (pin "84") (pinfunction "VDD_84") (pintype "power_in"))
      (node (ref "IC1") (pin "95") (pinfunction "VDD_95") (pintype "power_in"))
      (node (ref "IC2") (pin "3") (pinfunction "Vcc_3") (pintype "power_in"))
      (node (ref "JP1") (pin "1") (pinfunction "1_1") (pintype "passive"))
      (node (ref "JP2") (pin "1") (pinfunction "E1_1") (pintype "passive"))
      (node (ref "R1") (pin "1") (pinfunction "1_1") (pintype "passive"))
      (node (ref "R112") (pin "2") (pinfunction "2_2") (pintype "passive"))
      (node (ref "R113") (pin "2") (pinfunction "2_2") (pintype "passive"))
      (node (ref "R5") (pin "1") (pinfunction "1_1") (pintype "passive"))
      (node (ref "R6") (pin "1") (pinfunction "1_1") (pintype "passive"))
    )
    (net (code "113") (name "unconnected-(IC1A-PA8-Pad100)") (class "Default")
      (node (ref "IC1") (pin "100") (pinfunction "PA8_100") (pintype "bidirectional"))
    )
    (net (code "114") (name "unconnected-(IC1A-PB0-Pad46)") (class "Default")
      (node (ref "IC1") (pin "46") (pinfunction "PB0_46") (pintype "bidirectional"))
    )
    (net (code "115") (name "unconnected-(IC1A-PB1-Pad47)") (class "Default")
      (node (ref "IC1") (pin "47") (pinfunction "PB1_47") (pintype "bidirectional"))
    )
    (net (code "116") (name "unconnected-(IC1A-PB5-Pad135)") (class "Default")
      (node (ref "IC1") (pin "135") (pinfunction "PB5_135") (pintype "bidirectional"))
    )
    (net (code "117") (name "unconnected-(IC1A-PB10-Pad69)") (class "Default")
      (node (ref "IC1") (pin "69") (pinfunction "PB10_69") (pintype "bidirectional"))
    )
    (net (code "118") (name "unconnected-(IC1A-PB11-Pad70)") (class "Default")
      (node (ref "IC1") (pin "70") (pinfunction "PB11_70") (pintype "bidirectional"))
    )
    (net (code "119") (name "unconnected-(IC1A-PB14-Pad75)") (class "Default")
      (node (ref "IC1") (pin "75") (pinfunction "PB14_75") (pintype "bidirectional"))
    )
    (net (code "120") (name "unconnected-(IC1A-PC6-Pad96)") (class "Default")
      (node (ref "IC1") (pin "96") (pinfunction "PC6_96") (pintype "bidirectional"))
    )
    (net (code "121") (name "unconnected-(IC1A-PC7-Pad97)") (class "Default")
      (node (ref "IC1") (pin "97") (pinfunction "PC7_97") (pintype "bidirectional"))
    )
    (net (code "122") (name "unconnected-(IC1A-PC11-Pad112)") (class "Default")
      (node (ref "IC1") (pin "112") (pinfunction "PC11_112") (pintype "bidirectional"))
    )
    (net (code "123") (name "unconnected-(IC1A-PC12-Pad113)") (class "Default")
      (node (ref "IC1") (pin "113") (pinfunction "PC12_113") (pintype "bidirectional"))
    )
    (net (code "124") (name "unconnected-(IC1A-PC13-Pad7)") (class "Default")
      (node (ref "IC1") (pin "7") (pinfunction "PC13_7") (pintype "bidirectional"))
    )
    (net (code "125") (name "unconnected-(IC1A-PC14-OSC32_IN(PC14)-Pad8)") (class "Default")
      (node (ref "IC1") (pin "8") (pinfunction "PC14-OSC32_IN(PC14)_8") (pintype "bidirectional"))
    )
    (net (code "126") (name "unconnected-(IC1A-PC15-OSC32_OUT(PC15)-Pad9)") (class "Default")
      (node (ref "IC1") (pin "9") (pinfunction "PC15-OSC32_OUT(PC15)_9") (pintype "bidirectional"))
    )
    (net (code "127") (name "unconnected-(IC1A-PF0-Pad10)") (class "Default")
      (node (ref "IC1") (pin "10") (pinfunction "PF0_10") (pintype "bidirectional"))
    )
    (net (code "128") (name "unconnected-(IC1A-PF1-Pad11)") (class "Default")
      (node (ref "IC1") (pin "11") (pinfunction "PF1_11") (pintype "bidirectional"))
    )
    (net (code "129") (name "unconnected-(IC1A-PF2-Pad12)") (class "Default")
      (node (ref "IC1") (pin "12") (pinfunction "PF2_12") (pintype "bidirectional"))
    )
    (net (code "130") (name "unconnected-(IC1A-PF11-Pad49)") (class "Default")
      (node (ref "IC1") (pin "49") (pinfunction "PF11_49") (pintype "bidirectional"))
    )
    (net (code "131") (name "unconnected-(IC1A-PF12-Pad50)") (class "Default")
      (node (ref "IC1") (pin "50") (pinfunction "PF12_50") (pintype "bidirectional"))
    )
    (net (code "132") (name "unconnected-(IC1A-PF13-Pad53)") (class "Default")
      (node (ref "IC1") (pin "53") (pinfunction "PF13_53") (pintype "bidirectional"))
    )
    (net (code "133") (name "unconnected-(IC1A-PG2-Pad87)") (class "Default")
      (node (ref "IC1") (pin "87") (pinfunction "PG2_87") (pintype "bidirectional"))
    )
    (net (code "134") (name "unconnected-(IC1A-PG3-Pad88)") (class "Default")
      (node (ref "IC1") (pin "88") (pinfunction "PG3_88") (pintype "bidirectional"))
    )
    (net (code "135") (name "unconnected-(IC1A-PG7-Pad92)") (class "Default")
      (node (ref "IC1") (pin "92") (pinfunction "PG7_92") (pintype "bidirectional"))
    )
    (net (code "136") (name "unconnected-(IC1B-VBAT-Pad6)") (class "Default")
      (node (ref "IC1") (pin "6") (pinfunction "VBAT_6") (pintype "power_in"))
    )
    (net (code "137") (name "unconnected-(JP1-Pad7)") (class "Default")
      (node (ref "JP1") (pin "7") (pinfunction "7_7") (pintype "passive"))
    )
    (net (code "138") (name "unconnected-(JP1-Pad9)") (class "Default")
      (node (ref "JP1") (pin "9") (pinfunction "9_9") (pintype "passive"))
    )
  )
)
